# Calibration.net
KiCad netlist of a schematic drawn in Altium Designer
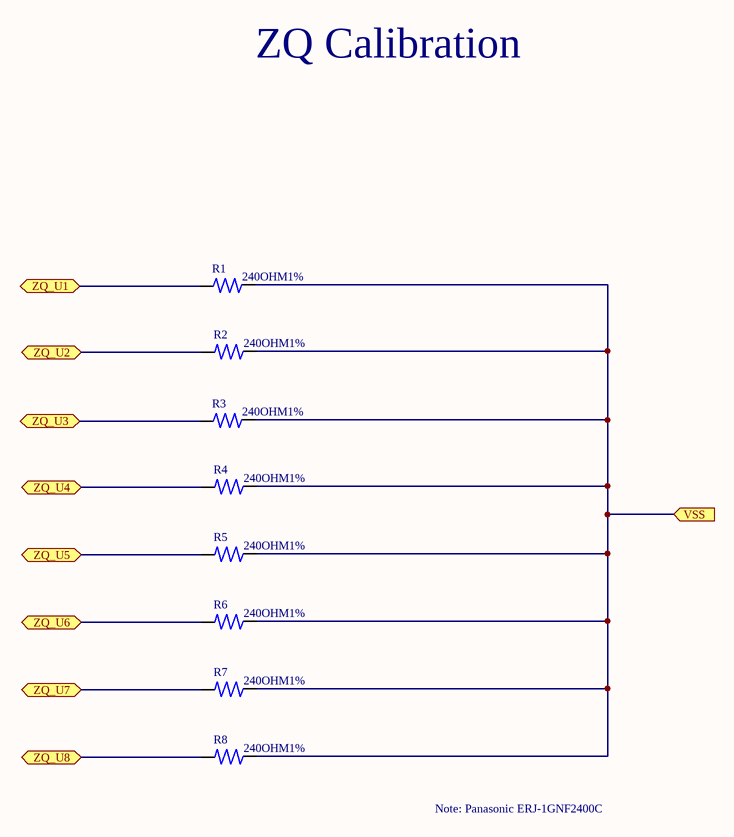
[diagram p0: Calibration.SchDoc]

(export (version "E")
  (design (tool "Eeschema 10.0.6"))
  (components
    (comp (ref "R1")
      (value "Resistor 0402")
      (footprint "Resistor 0402")
      (fields
        (field (name "MANUFACTURER") "Vishay")
        (field (name "MANUFACTURER PART NUMBER") "CRCW060310K0FKEA")
        (field (name "TOLERANCE") "1%")
        (field (name "RESISTANCE") "240OHM1%")
      )
      (libsource (lib "RouterIntLib") (part "Resistor 0201"))
    )
    (comp (ref "R2")
      (value "Resistor 0402")
      (footprint "Resistor 0402")
      (fields
        (field (name "MANUFACTURER") "Vishay")
        (field (name "MANUFACTURER PART NUMBER") "CRCW060310K0FKEA")
        (field (name "TOLERANCE") "1%")
        (field (name "RESISTANCE") "240OHM1%")
      )
      (libsource (lib "RouterIntLib") (part "Resistor 0201"))
    )
    (comp (ref "R3")
      (value "Resistor 0402")
      (footprint "Resistor 0402")
      (fields
        (field (name "MANUFACTURER") "Vishay")
        (field (name "MANUFACTURER PART NUMBER") "CRCW060310K0FKEA")
        (field (name "TOLERANCE") "1%")
        (field (name "RESISTANCE") "240OHM1%")
      )
      (libsource (lib "RouterIntLib") (part "Resistor 0201"))
    )
    (comp (ref "R4")
      (value "Resistor 0402")
      (footprint "Resistor 0402")
      (fields
        (field (name "MANUFACTURER") "Vishay")
        (field (name "MANUFACTURER PART NUMBER") "CRCW060310K0FKEA")
        (field (name "TOLERANCE") "1%")
        (field (name "RESISTANCE") "240OHM1%")
      )
      (libsource (lib "RouterIntLib") (part "Resistor 0201"))
    )
    (comp (ref "R5")
      (value "Resistor 0402")
      (footprint "Resistor 0402")
      (fields
        (field (name "MANUFACTURER") "Vishay")
        (field (name "MANUFACTURER PART NUMBER") "CRCW060310K0FKEA")
        (field (name "TOLERANCE") "1%")
        (field (name "RESISTANCE") "240OHM1%")
      )
      (libsource (lib "RouterIntLib") (part "Resistor 0201"))
    )
    (comp (ref "R6")
      (value "Resistor 0402")
      (footprint "Resistor 0402")
      (fields
        (field (name "MANUFACTURER") "Vishay")
        (field (name "MANUFACTURER PART NUMBER") "CRCW060310K0FKEA")
        (field (name "TOLERANCE") "1%")
        (field (name "RESISTANCE") "240OHM1%")
      )
      (libsource (lib "RouterIntLib") (part "Resistor 0201"))
    )
    (comp (ref "R7")
      (value "Resistor 0402")
      (footprint "Resistor 0402")
      (fields
        (field (name "MANUFACTURER") "Vishay")
        (field (name "MANUFACTURER PART NUMBER") "CRCW060310K0FKEA")
        (field (name "TOLERANCE") "1%")
        (field (name "RESISTANCE") "240OHM1%")
      )
      (libsource (lib "RouterIntLib") (part "Resistor 0201"))
    )
    (comp (ref "R8")
      (value "Resistor 0402")
      (footprint "Resistor 0402")
      (fields
        (field (name "MANUFACTURER") "Vishay")
        (field (name "MANUFACTURER PART NUMBER") "CRCW060310K0FKEA")
        (field (name "TOLERANCE") "1%")
        (field (name "RESISTANCE") "240OHM1%")
      )
      (libsource (lib "RouterIntLib") (part "Resistor 0201"))
    )
  )
  (nets
    (net (code "1") (name "/VSS") (class "Default")
      (node (ref "R1") (pin "2") (pinfunction "2_2") (pintype "passive"))
      (node (ref "R2") (pin "2") (pinfunction "2_2") (pintype "passive"))
      (node (ref "R3") (pin "2") (pinfunction "2_2") (pintype "passive"))
      (node (ref "R4") (pin "2") (pinfunction "2_2") (pintype "passive"))
      (node (ref "R5") (pin "2") (pinfunction "2_2") (pintype "passive"))
      (node (ref "R6") (pin "2") (pinfunction "2_2") (pintype "passive"))
      (node (ref "R7") (pin "2") (pinfunction "2_2") (pintype "passive"))
      (node (ref "R8") (pin "2") (pinfunction "2_2") (pintype "passive"))
    )
    (net (code "2") (name "/ZQ_U1") (class "Default")
      (node (ref "R1") (pin "1") (pinfunction "1_1") (pintype "passive"))
    )
    (net (code "3") (name "/ZQ_U2") (class "Default")
      (node (ref "R2") (pin "1") (pinfunction "1_1") (pintype "passive"))
    )
    (net (code "4") (name "/ZQ_U3") (class "Default")
      (node (ref "R3") (pin "1") (pinfunction "1_1") (pintype "passive"))
    )
    (net (code "5") (name "/ZQ_U4") (class "Default")
      (node (ref "R4") (pin "1") (pinfunction "1_1") (pintype "passive"))
    )
    (net (code "6") (name "/ZQ_U5") (class "Default")
      (node (ref "R5") (pin "1") (pinfunction "1_1") (pintype "passive"))
    )
    (net (code "7") (name "/ZQ_U6") (class "Default")
      (node (ref "R6") (pin "1") (pinfunction "1_1") (pintype "passive"))
    )
    (net (code "8") (name "/ZQ_U7") (class "Default")
      (node (ref "R7") (pin "1") (pinfunction "1_1") (pintype "passive"))
    )
    (net (code "9") (name "/ZQ_U8") (class "Default")
      (node (ref "R8") (pin "1") (pinfunction "1_1") (pintype "passive"))
    )
  )
)
